# DCDC_Converter.net
KiCad netlist of a schematic drawn in Altium Designer
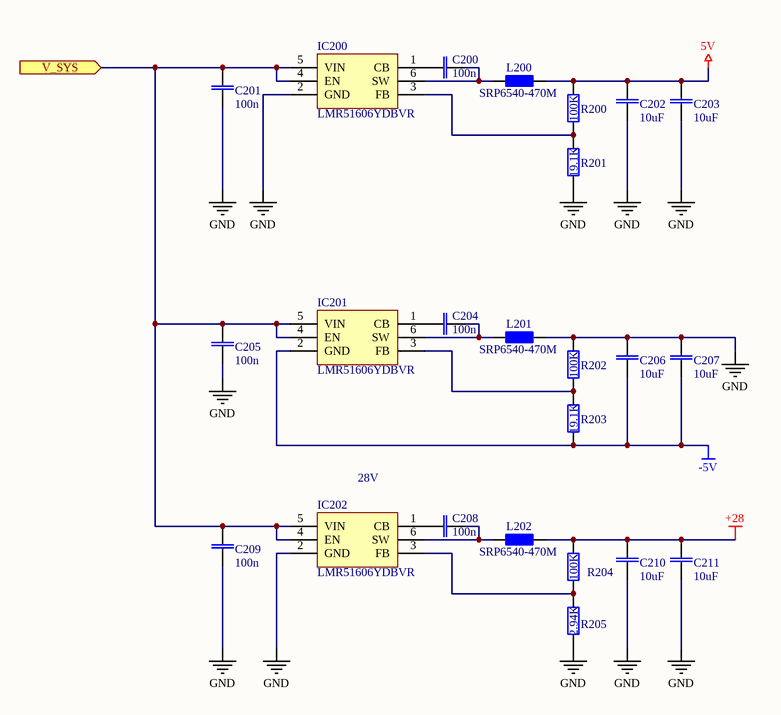
[diagram p0: DCDC_Converter.SchDoc]

(export (version "E")
  (design (tool "Eeschema 10.0.6"))
  (components
    (comp (ref "C200")
      (value "100n")
      (footprint "CAP0402")
      (fields (field (name "MPN") "CL05A104KA5NNNC") (field (name "TOLERANCE") "10%"))
      (libsource (lib "Schematic") (part "CL05A104KA5NNNC"))
    )
    (comp (ref "C201")
      (value "100n")
      (footprint "CAP0402")
      (fields (field (name "MPN") "CL05A104KA5NNNC") (field (name "TOLERANCE") "10%"))
      (libsource (lib "Schematic") (part "CL05A104KA5NNNC"))
    )
    (comp (ref "C202")
      (value "10uF")
      (footprint "CAP0402")
      (fields (field (name "MPN") "CC0402KRX7R9BB222"))
      (libsource (lib "Passive") (part "GRM155R61A106ME11D"))
    )
    (comp (ref "C203")
      (value "10uF")
      (footprint "CAP0402")
      (fields (field (name "MPN") "CC0402KRX7R9BB222"))
      (libsource (lib "Passive") (part "GRM155R61A106ME11D"))
    )
    (comp (ref "C204")
      (value "100n")
      (footprint "CAP0402")
      (fields (field (name "MPN") "CL05A104KA5NNNC") (field (name "TOLERANCE") "10%"))
      (libsource (lib "Schematic") (part "CL05A104KA5NNNC"))
    )
    (comp (ref "C205")
      (value "100n")
      (footprint "CAP0402")
      (fields (field (name "MPN") "CL05A104KA5NNNC") (field (name "TOLERANCE") "10%"))
      (libsource (lib "Schematic") (part "CL05A104KA5NNNC"))
    )
    (comp (ref "C206")
      (value "10uF")
      (footprint "CAP0402")
      (fields (field (name "MPN") "CC0402KRX7R9BB222"))
      (libsource (lib "Passive") (part "GRM155R61A106ME11D"))
    )
    (comp (ref "C207")
      (value "10uF")
      (footprint "CAP0402")
      (fields (field (name "MPN") "CC0402KRX7R9BB222"))
      (libsource (lib "Passive") (part "GRM155R61A106ME11D"))
    )
    (comp (ref "C208")
      (value "100n")
      (footprint "CAP0402")
      (fields (field (name "MPN") "CL05A104KA5NNNC") (field (name "TOLERANCE") "10%"))
      (libsource (lib "Schematic") (part "CL05A104KA5NNNC"))
    )
    (comp (ref "C209")
      (value "100n")
      (footprint "CAP0402")
      (fields (field (name "MPN") "CL05A104KA5NNNC") (field (name "TOLERANCE") "10%"))
      (libsource (lib "Schematic") (part "CL05A104KA5NNNC"))
    )
    (comp (ref "C210")
      (value "10uF")
      (footprint "CAP0603")
      (fields (field (name "MPN") "CL05A475MP5NRNC") (field (name "TOLERANCE") "20%"))
      (libsource (lib "Passive") (part "GRM188R6YA106MA73D"))
    )
    (comp (ref "C211")
      (value "10uF")
      (footprint "CAP0603")
      (fields (field (name "MPN") "CL05A475MP5NRNC") (field (name "TOLERANCE") "20%"))
      (libsource (lib "Passive") (part "GRM188R6YA106MA73D"))
    )
    (comp (ref "IC200")
      (value "LMR51606YDBVR")
      (footprint "SOT95P245X120-6N")
      (libsource (lib "Schematic") (part "LMR51606YDBVR"))
    )
    (comp (ref "IC201")
      (value "LMR51606YDBVR")
      (footprint "SOT95P245X120-6N")
      (libsource (lib "Schematic") (part "LMR51606YDBVR"))
    )
    (comp (ref "IC202")
      (value "LMR51606YDBVR")
      (footprint "SOT95P245X120-6N")
      (libsource (lib "Schematic") (part "LMR51606YDBVR"))
    )
    (comp (ref "L200")
      (value "SRP6540-470M")
      (footprint "SRP6540")
      (libsource (lib "Passive") (part "SRP6540-470M"))
    )
    (comp (ref "L201")
      (value "SRP6540-470M")
      (footprint "SRP6540")
      (libsource (lib "Passive") (part "SRP6540-470M"))
    )
    (comp (ref "L202")
      (value "SRP6540-470M")
      (footprint "SRP6540")
      (libsource (lib "Passive") (part "SRP6540-470M"))
    )
    (comp (ref "R200")
      (value "RC0402FR-07100KL")
      (footprint "RES0402")
      (libsource (lib "Passive") (part "RC0402FR-07100KL"))
    )
    (comp (ref "R201")
      (value "RC0402FR-0719K1L")
      (footprint "RES0402")
      (libsource (lib "Passive") (part "RC0402FR-0719K1L"))
    )
    (comp (ref "R202")
      (value "RC0402FR-07100KL")
      (footprint "RES0402")
      (libsource (lib "Passive") (part "RC0402FR-07100KL"))
    )
    (comp (ref "R203")
      (value "RC0402FR-0719K1L")
      (footprint "RES0402")
      (libsource (lib "Passive") (part "RC0402FR-0719K1L"))
    )
    (comp (ref "R204")
      (value "RC0402FR-07100KL")
      (footprint "RES0402")
      (libsource (lib "Passive") (part "RC0402FR-07100KL"))
    )
    (comp (ref "R205")
      (value "RC0402FR-072K94L")
      (footprint "RES0402")
      (libsource (lib "Passive") (part "RC0402FR-072K94L"))
    )
  )
  (nets
    (net (code "1") (name "+28") (class "Default")
      (node (ref "C210") (pin "2") (pinfunction "2_2") (pintype "passive"))
      (node (ref "C211") (pin "2") (pinfunction "2_2") (pintype "passive"))
      (node (ref "L202") (pin "2") (pinfunction "2_2") (pintype "passive"))
      (node (ref "R204") (pin "2") (pinfunction "2_2") (pintype "passive"))
    )
    (net (code "2") (name "-5V") (class "Default")
      (node (ref "C206") (pin "1") (pinfunction "1_1") (pintype "passive"))
      (node (ref "C207") (pin "1") (pinfunction "1_1") (pintype "passive"))
      (node (ref "IC201") (pin "2") (pinfunction "GND_2") (pintype "passive"))
      (node (ref "R203") (pin "1") (pinfunction "1_1") (pintype "passive"))
    )
    (net (code "3") (name "/V_SYS") (class "Default")
      (node (ref "C201") (pin "1") (pinfunction "1_1") (pintype "passive"))
      (node (ref "C205") (pin "1") (pinfunction "1_1") (pintype "passive"))
      (node (ref "C209") (pin "1") (pinfunction "1_1") (pintype "passive"))
      (node (ref "IC200") (pin "4") (pinfunction "EN_4") (pintype "passive"))
      (node (ref "IC200") (pin "5") (pinfunction "VIN_5") (pintype "passive"))
      (node (ref "IC201") (pin "4") (pinfunction "EN_4") (pintype "passive"))
      (node (ref "IC201") (pin "5") (pinfunction "VIN_5") (pintype "passive"))
      (node (ref "IC202") (pin "4") (pinfunction "EN_4") (pintype "passive"))
      (node (ref "IC202") (pin "5") (pinfunction "VIN_5") (pintype "passive"))
    )
    (net (code "4") (name "5V") (class "Default")
      (node (ref "C202") (pin "2") (pinfunction "2_2") (pintype "passive"))
      (node (ref "C203") (pin "2") (pinfunction "2_2") (pintype "passive"))
      (node (ref "L200") (pin "2") (pinfunction "2_2") (pintype "passive"))
      (node (ref "R200") (pin "2") (pinfunction "2_2") (pintype "passive"))
    )
    (net (code "5") (name "GND") (class "Default")
      (node (ref "C201") (pin "2") (pinfunction "2_2") (pintype "passive"))
      (node (ref "C202") (pin "1") (pinfunction "1_1") (pintype "passive"))
      (node (ref "C203") (pin "1") (pinfunction "1_1") (pintype "passive"))
      (node (ref "C205") (pin "2") (pinfunction "2_2") (pintype "passive"))
      (node (ref "C206") (pin "2") (pinfunction "2_2") (pintype "passive"))
      (node (ref "C207") (pin "2") (pinfunction "2_2") (pintype "passive"))
      (node (ref "C209") (pin "2") (pinfunction "2_2") (pintype "passive"))
      (node (ref "C210") (pin "1") (pinfunction "1_1") (pintype "passive"))
      (node (ref "C211") (pin "1") (pinfunction "1_1") (pintype "passive"))
      (node (ref "IC200") (pin "2") (pinfunction "GND_2") (pintype "passive"))
      (node (ref "IC202") (pin "2") (pinfunction "GND_2") (pintype "passive"))
      (node (ref "L201") (pin "2") (pinfunction "2_2") (pintype "passive"))
      (node (ref "R201") (pin "1") (pinfunction "1_1") (pintype "passive"))
      (node (ref "R202") (pin "2") (pinfunction "2_2") (pintype "passive"))
      (node (ref "R205") (pin "1") (pinfunction "1_1") (pintype "passive"))
    )
    (net (code "6") (name "Net-(IC200-CB)") (class "Default")
      (node (ref "C200") (pin "2") (pinfunction "2_2") (pintype "passive"))
      (node (ref "IC200") (pin "1") (pinfunction "CB_1") (pintype "passive"))
    )
    (net (code "7") (name "Net-(IC200-FB)") (class "Default")
      (node (ref "IC200") (pin "3") (pinfunction "FB_3") (pintype "passive"))
      (node (ref "R200") (pin "1") (pinfunction "1_1") (pintype "passive"))
      (node (ref "R201") (pin "2") (pinfunction "2_2") (pintype "passive"))
    )
    (net (code "8") (name "Net-(IC200-SW)") (class "Default")
      (node (ref "C200") (pin "1") (pinfunction "1_1") (pintype "passive"))
      (node (ref "IC200") (pin "6") (pinfunction "SW_6") (pintype "passive"))
      (node (ref "L200") (pin "1") (pinfunction "1_1") (pintype "passive"))
    )
    (net (code "9") (name "Net-(IC201-CB)") (class "Default")
      (node (ref "C204") (pin "2") (pinfunction "2_2") (pintype "passive"))
      (node (ref "IC201") (pin "1") (pinfunction "CB_1") (pintype "passive"))
    )
    (net (code "10") (name "Net-(IC201-FB)") (class "Default")
      (node (ref "IC201") (pin "3") (pinfunction "FB_3") (pintype "passive"))
      (node (ref "R202") (pin "1") (pinfunction "1_1") (pintype "passive"))
      (node (ref "R203") (pin "2") (pinfunction "2_2") (pintype "passive"))
    )
    (net (code "11") (name "Net-(IC201-SW)") (class "Default")
      (node (ref "C204") (pin "1") (pinfunction "1_1") (pintype "passive"))
      (node (ref "IC201") (pin "6") (pinfunction "SW_6") (pintype "passive"))
      (node (ref "L201") (pin "1") (pinfunction "1_1") (pintype "passive"))
    )
    (net (code "12") (name "Net-(IC202-CB)") (class "Default")
      (node (ref "C208") (pin "2") (pinfunction "2_2") (pintype "passive"))
      (node (ref "IC202") (pin "1") (pinfunction "CB_1") (pintype "passive"))
    )
    (net (code "13") (name "Net-(IC202-FB)") (class "Default")
      (node (ref "IC202") (pin "3") (pinfunction "FB_3") (pintype "passive"))
      (node (ref "R204") (pin "1") (pinfunction "1_1") (pintype "passive"))
      (node (ref "R205") (pin "2") (pinfunction "2_2") (pintype "passive"))
    )
    (net (code "14") (name "Net-(IC202-SW)") (class "Default")
      (node (ref "C208") (pin "1") (pinfunction "1_1") (pintype "passive"))
      (node (ref "IC202") (pin "6") (pinfunction "SW_6") (pintype "passive"))
      (node (ref "L202") (pin "1") (pinfunction "1_1") (pintype "passive"))
    )
  )
)
